# Place_3D_Body.net
KiCad netlist of a schematic drawn in Altium Designer
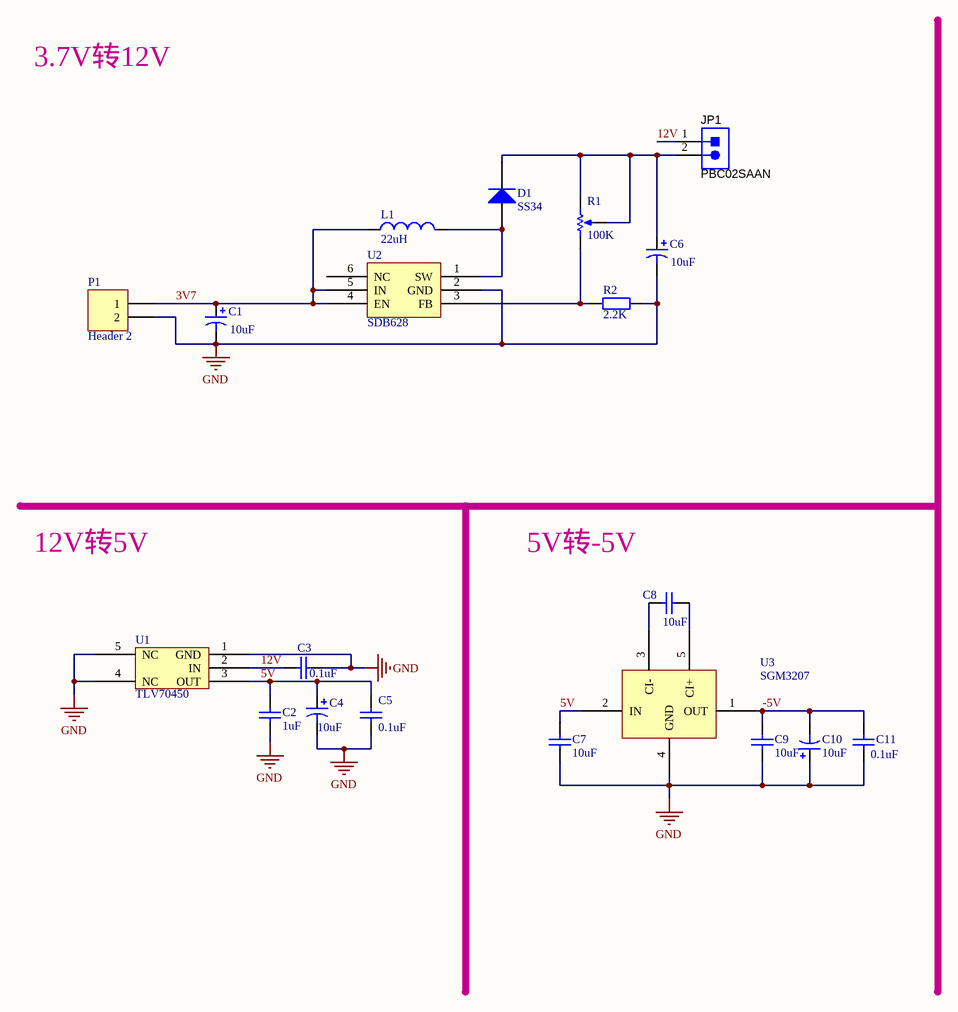
[diagram p0: Place_3D_Body.SchDoc]

(export (version "E")
  (design (tool "Eeschema 10.0.6"))
  (components
    (comp (ref "C1")
      (value "10uF")
      (footprint "tan-a")
      (description "Polarized Capacitor (Radial)")
      (fields (field (name "Comment") "Cap Pol1") (field (name "PUBLISHER") "Altium Limited"))
      (libsource (lib "Miscellaneous Devices") (part "Cap Pol1"))
    )
    (comp (ref "C2")
      (value "1uF")
      (footprint "C-0603")
      (description "Capacitor")
      (fields (field (name "Comment") "Cap") (field (name "PUBLISHER") "Altium Limited"))
      (libsource (lib "Miscellaneous Devices") (part "Cap"))
    )
    (comp (ref "C3")
      (value "0.1uF")
      (footprint "C-0603")
      (description "Capacitor")
      (fields (field (name "Comment") "Cap") (field (name "PUBLISHER") "Altium Limited"))
      (libsource (lib "Miscellaneous Devices") (part "Cap"))
    )
    (comp (ref "C4")
      (value "10uF")
      (footprint "tan-a")
      (description "Polarized Capacitor (Radial)")
      (fields (field (name "Comment") "Cap Pol1") (field (name "PUBLISHER") "Altium Limited"))
      (libsource (lib "Miscellaneous Devices") (part "Cap Pol1"))
    )
    (comp (ref "C5")
      (value "0.1uF")
      (footprint "C-0603")
      (description "Capacitor")
      (fields (field (name "Comment") "Cap") (field (name "PUBLISHER") "Altium Limited"))
      (libsource (lib "Miscellaneous Devices") (part "Cap"))
    )
    (comp (ref "C6")
      (value "10uF")
      (footprint "tan-a")
      (description "Polarized Capacitor (Radial)")
      (fields (field (name "Comment") "Cap Pol1") (field (name "PUBLISHER") "Altium Limited"))
      (libsource (lib "Miscellaneous Devices") (part "Cap Pol1"))
    )
    (comp (ref "C7")
      (value "10uF")
      (footprint "C-0603")
      (description "Capacitor")
      (fields (field (name "Comment") "Cap") (field (name "PUBLISHER") "Altium Limited"))
      (libsource (lib "Miscellaneous Devices") (part "Cap"))
    )
    (comp (ref "C8")
      (value "10uF")
      (footprint "C-0603")
      (description "Capacitor")
      (fields (field (name "Comment") "Cap") (field (name "PUBLISHER") "Altium Limited"))
      (libsource (lib "Miscellaneous Devices") (part "Cap"))
    )
    (comp (ref "C9")
      (value "10uF")
      (footprint "C-0603")
      (description "Capacitor")
      (fields (field (name "Comment") "Cap") (field (name "PUBLISHER") "Altium Limited"))
      (libsource (lib "Miscellaneous Devices") (part "Cap"))
    )
    (comp (ref "C10")
      (value "10uF")
      (footprint "TAN-A")
      (description "Polarized Capacitor (Radial)")
      (fields (field (name "Comment") "Cap Pol1") (field (name "PUBLISHER") "Altium Limited"))
      (libsource (lib "Miscellaneous Devices") (part "Cap Pol1"))
    )
    (comp (ref "C11")
      (value "0.1uF")
      (footprint "C-0603")
      (description "Capacitor")
      (fields (field (name "Comment") "Cap") (field (name "PUBLISHER") "Altium Limited"))
      (libsource (lib "Miscellaneous Devices") (part "Cap"))
    )
    (comp (ref "D1")
      (value "SS34")
      (footprint "LC-SMA(DO-214AC)_S2")
      (description "Default Diode")
      (fields (field (name "PUBLISHER") "Altium Limited"))
      (libsource (lib "Miscellaneous Devices") (part "Diode"))
    )
    (comp (ref "JP1")
      (value "PBC02SAAN")
      (footprint "Sullins_PBC02SAAN")
      (description "Header, 100mil, 2x1, Gold, TH")
      (fields
        (field (name "MANUFACTURER") "Sullins Connector Solutions")
        (field (name "SYMBOLCREATOR") "a0412235")
        (field (name "PUBLISHER") "Texas Instruments")
      )
      (libsource (lib "Connectors_Sullins") (part "PBC02SAAN"))
    )
    (comp (ref "L1")
      (value "22uH")
      (footprint "SMDRH105R")
      (description "Inductor")
      (fields (field (name "Comment") "SMDRH105R-220MT") (field (name "PUBLISHER") "Altium Limited"))
      (libsource (lib "Miscellaneous Devices") (part "Inductor"))
    )
    (comp (ref "P1")
      (value "Header 2")
      (footprint "POWER-p2")
      (description "Header, 2-Pin")
      (fields (field (name "PUBLISHER") "Altium Limited"))
      (libsource (lib "Miscellaneous Connectors") (part "Header 2"))
    )
    (comp (ref "R1")
      (value "100K")
      (footprint "rp-3296-w")
      (description "Potentiometer")
      (fields (field (name "Comment") "RPot") (field (name "PUBLISHER") "Altium Limited"))
      (libsource (lib "Miscellaneous Devices") (part "RPot"))
    )
    (comp (ref "R2")
      (value "2.2K")
      (footprint "r-0603")
      (description "Resistor")
      (fields (field (name "Comment") "Res2") (field (name "PUBLISHER") "Altium Limited"))
      (libsource (lib "Miscellaneous Devices") (part "Res2"))
    )
    (comp (ref "U1") (value "TLV70450") (footprint "SOT-23-5") (libsource (lib "AddMore") (part "TLV704")))
    (comp (ref "U2") (value "SDB628") (footprint "sot-23-6") (libsource (lib "AddMore") (part "SDB628")))
    (comp (ref "U3") (value "SGM3207") (footprint "SOT-23-5") (libsource (lib "AddMore") (part "TPS6040x")))
  )
  (nets
    (net (code "1") (name "/-5V") (class "Default")
      (node (ref "C10") (pin "2") (pinfunction "2_2") (pintype "passive"))
      (node (ref "C11") (pin "1") (pinfunction "1_1") (pintype "passive"))
      (node (ref "C9") (pin "2") (pinfunction "2_2") (pintype "passive"))
      (node (ref "U3") (pin "1") (pinfunction "OUT_1") (pintype "passive"))
    )
    (net (code "2") (name "/3V7") (class "Default")
      (node (ref "C1") (pin "1") (pinfunction "1_1") (pintype "passive"))
      (node (ref "L1") (pin "2") (pinfunction "2_2") (pintype "passive"))
      (node (ref "P1") (pin "1") (pinfunction "1_1") (pintype "passive"))
      (node (ref "U2") (pin "4") (pinfunction "EN_4") (pintype "passive"))
      (node (ref "U2") (pin "5") (pinfunction "IN_5") (pintype "passive"))
    )
    (net (code "3") (name "/5V") (class "Default")
      (node (ref "C2") (pin "2") (pinfunction "2_2") (pintype "passive"))
      (node (ref "C4") (pin "1") (pinfunction "1_1") (pintype "passive"))
      (node (ref "C5") (pin "1") (pinfunction "1_1") (pintype "passive"))
      (node (ref "C7") (pin "2") (pinfunction "2_2") (pintype "passive"))
      (node (ref "U1") (pin "3") (pinfunction "OUT_3") (pintype "passive"))
      (node (ref "U3") (pin "2") (pinfunction "IN_2") (pintype "passive"))
    )
    (net (code "4") (name "/12V") (class "Default")
      (node (ref "C3") (pin "2") (pinfunction "2_2") (pintype "passive"))
      (node (ref "JP1") (pin "1") (pinfunction "1_1") (pintype "passive"))
      (node (ref "U1") (pin "2") (pinfunction "IN_2") (pintype "passive"))
    )
    (net (code "5") (name "GND") (class "Default")
      (node (ref "C1") (pin "2") (pinfunction "2_2") (pintype "passive"))
      (node (ref "C10") (pin "1") (pinfunction "1_1") (pintype "passive"))
      (node (ref "C11") (pin "2") (pinfunction "2_2") (pintype "passive"))
      (node (ref "C2") (pin "1") (pinfunction "1_1") (pintype "passive"))
      (node (ref "C3") (pin "1") (pinfunction "1_1") (pintype "passive"))
      (node (ref "C4") (pin "2") (pinfunction "2_2") (pintype "passive"))
      (node (ref "C5") (pin "2") (pinfunction "2_2") (pintype "passive"))
      (node (ref "C6") (pin "2") (pinfunction "2_2") (pintype "passive"))
      (node (ref "C7") (pin "1") (pinfunction "1_1") (pintype "passive"))
      (node (ref "C9") (pin "1") (pinfunction "1_1") (pintype "passive"))
      (node (ref "P1") (pin "2") (pinfunction "2_2") (pintype "passive"))
      (node (ref "R2") (pin "2") (pinfunction "2_2") (pintype "passive"))
      (node (ref "U1") (pin "1") (pinfunction "GND_1") (pintype "passive"))
      (node (ref "U1") (pin "4") (pinfunction "NC_4") (pintype "passive"))
      (node (ref "U1") (pin "5") (pinfunction "NC_5") (pintype "passive"))
      (node (ref "U2") (pin "2") (pinfunction "GND_2") (pintype "passive"))
      (node (ref "U3") (pin "4") (pinfunction "GND_4") (pintype "passive"))
    )
    (net (code "6") (name "Net-(D1-A)") (class "Default")
      (node (ref "D1") (pin "1") (pinfunction "A_1") (pintype "passive"))
      (node (ref "L1") (pin "1") (pinfunction "1_1") (pintype "passive"))
      (node (ref "U2") (pin "1") (pinfunction "SW_1") (pintype "passive"))
    )
    (net (code "7") (name "Net-(D1-K)") (class "Default")
      (node (ref "C6") (pin "1") (pinfunction "1_1") (pintype "passive"))
      (node (ref "D1") (pin "2") (pinfunction "K_2") (pintype "passive"))
      (node (ref "JP1") (pin "2") (pinfunction "2_2") (pintype "passive"))
      (node (ref "R1") (pin "2") (pinfunction "BOT_2") (pintype "passive"))
      (node (ref "R1") (pin "3") (pinfunction "TAP_3") (pintype "passive"))
    )
    (net (code "8") (name "Net-(R1-TOP)") (class "Default")
      (node (ref "R1") (pin "1") (pinfunction "TOP_1") (pintype "passive"))
      (node (ref "R2") (pin "1") (pinfunction "1_1") (pintype "passive"))
      (node (ref "U2") (pin "3") (pinfunction "FB_3") (pintype "passive"))
    )
    (net (code "9") (name "Net-(U3-CI+)") (class "Default")
      (node (ref "C8") (pin "2") (pinfunction "2_2") (pintype "passive"))
      (node (ref "U3") (pin "5") (pinfunction "CI+_5") (pintype "passive"))
    )
    (net (code "10") (name "Net-(U3-CI-)") (class "Default")
      (node (ref "C8") (pin "1") (pinfunction "1_1") (pintype "passive"))
      (node (ref "U3") (pin "3") (pinfunction "CI-_3") (pintype "passive"))
    )
    (net (code "11") (name "unconnected-(U2-NC-Pad6)") (class "Default")
      (node (ref "U2") (pin "6") (pinfunction "NC_6") (pintype "passive"))
    )
  )
)
